# Electronic_Board_Schematic.net
KiCad netlist of a schematic drawn in Altium Designer
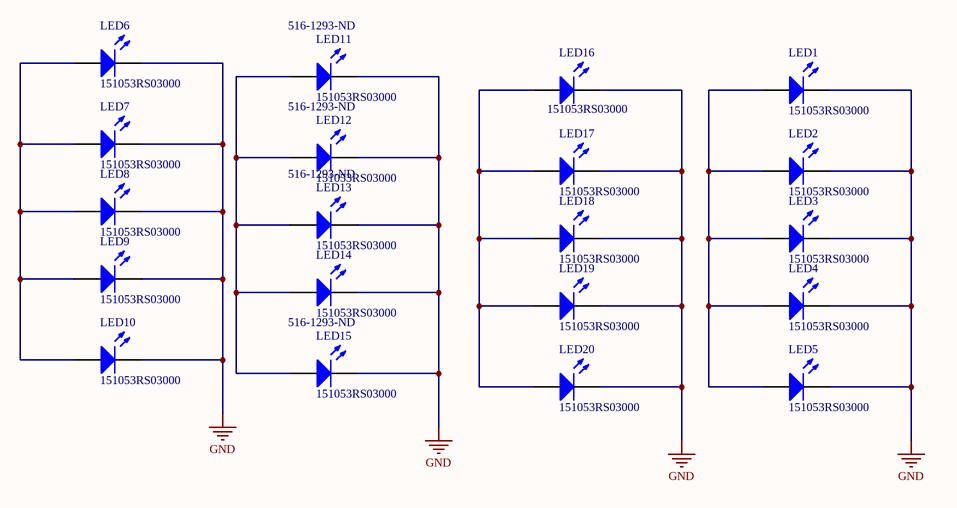
[diagram p0: Electronic_Board_Schematic.SchDoc]

(export (version "E")
  (design (tool "Eeschema 10.0.6"))
  (components
    (comp (ref "LED1")
      (value "151053RS03000")
      (footprint "Type 5mm")
      (description "THT LED round mono-color waterclear,  WL-TMRW ,Red")
      (fields (field (name "MANUFACTURER") "Wuerth Elektronik"))
      (libsource (lib "Altium Content Vault") (part "WE-LED_K1A2-2"))
    )
    (comp (ref "LED2")
      (value "151053RS03000")
      (footprint "Type 5mm")
      (description "THT LED round mono-color waterclear,  WL-TMRW ,Red")
      (fields (field (name "MANUFACTURER") "Wuerth Elektronik"))
      (libsource (lib "Altium Content Vault") (part "WE-LED_K1A2-2"))
    )
    (comp (ref "LED3")
      (value "151053RS03000")
      (footprint "Type 5mm")
      (description "THT LED round mono-color waterclear,  WL-TMRW ,Red")
      (fields (field (name "MANUFACTURER") "Wuerth Elektronik"))
      (libsource (lib "Altium Content Vault") (part "WE-LED_K1A2-2"))
    )
    (comp (ref "LED4")
      (value "151053RS03000")
      (footprint "Type 5mm")
      (description "THT LED round mono-color waterclear,  WL-TMRW ,Red")
      (fields (field (name "MANUFACTURER") "Wuerth Elektronik"))
      (libsource (lib "Altium Content Vault") (part "WE-LED_K1A2-2"))
    )
    (comp (ref "LED5")
      (value "151053RS03000")
      (footprint "Type 5mm")
      (description "THT LED round mono-color waterclear,  WL-TMRW ,Red")
      (fields (field (name "MANUFACTURER") "Wuerth Elektronik"))
      (libsource (lib "Altium Content Vault") (part "WE-LED_K1A2-2"))
    )
    (comp (ref "LED6")
      (value "151053RS03000")
      (footprint "Type 5mm")
      (description "THT LED round mono-color waterclear,  WL-TMRW ,Red")
      (fields (field (name "MANUFACTURER") "Wuerth Elektronik"))
      (libsource (lib "Altium Content Vault") (part "WE-LED_K1A2-2"))
    )
    (comp (ref "LED7")
      (value "151053RS03000")
      (footprint "Type 5mm")
      (description "THT LED round mono-color waterclear,  WL-TMRW ,Red")
      (fields (field (name "MANUFACTURER") "Wuerth Elektronik"))
      (libsource (lib "Altium Content Vault") (part "WE-LED_K1A2-2"))
    )
    (comp (ref "LED8")
      (value "151053RS03000")
      (footprint "Type 5mm")
      (description "THT LED round mono-color waterclear,  WL-TMRW ,Red")
      (fields (field (name "MANUFACTURER") "Wuerth Elektronik"))
      (libsource (lib "Altium Content Vault") (part "WE-LED_K1A2-2"))
    )
    (comp (ref "LED9")
      (value "151053RS03000")
      (footprint "Type 5mm")
      (description "THT LED round mono-color waterclear,  WL-TMRW ,Red")
      (fields (field (name "MANUFACTURER") "Wuerth Elektronik"))
      (libsource (lib "Altium Content Vault") (part "WE-LED_K1A2-2"))
    )
    (comp (ref "LED10")
      (value "151053RS03000")
      (footprint "Type 5mm")
      (description "THT LED round mono-color waterclear,  WL-TMRW ,Red")
      (fields (field (name "MANUFACTURER") "Wuerth Elektronik"))
      (libsource (lib "Altium Content Vault") (part "WE-LED_K1A2-2"))
    )
    (comp (ref "LED11")
      (value "151053RS03000")
      (footprint "Type 5mm")
      (description "THT LED round mono-color waterclear,  WL-TMRW ,Red")
      (fields
        (field (name "MANUFACTURER") "Wuerth Elektronik")
        (field (name "SUPPLIER PART NUMBER 1") "516-1293-ND")
        (field (name "MANUFACTURER PART NUMBER") "HLMP-1503")
      )
      (libsource (lib "Altium Content Vault") (part "WE-LED_K1A2-2"))
    )
    (comp (ref "LED12")
      (value "151053RS03000")
      (footprint "Type 5mm")
      (description "THT LED round mono-color waterclear,  WL-TMRW ,Red")
      (fields
        (field (name "MANUFACTURER") "Wuerth Elektronik")
        (field (name "SUPPLIER PART NUMBER 1") "516-1293-ND")
        (field (name "MANUFACTURER PART NUMBER") "HLMP-1503")
      )
      (libsource (lib "Altium Content Vault") (part "WE-LED_K1A2-2"))
    )
    (comp (ref "LED13")
      (value "151053RS03000")
      (footprint "Type 5mm")
      (description "THT LED round mono-color waterclear,  WL-TMRW ,Red")
      (fields
        (field (name "MANUFACTURER") "Wuerth Elektronik")
        (field (name "SUPPLIER PART NUMBER 1") "516-1293-ND")
        (field (name "MANUFACTURER PART NUMBER") "HLMP-1503")
      )
      (libsource (lib "Altium Content Vault") (part "WE-LED_K1A2-2"))
    )
    (comp (ref "LED14")
      (value "151053RS03000")
      (footprint "Type 5mm")
      (description "THT LED round mono-color waterclear,  WL-TMRW ,Red")
      (fields (field (name "MANUFACTURER") "Wuerth Elektronik"))
      (libsource (lib "Altium Content Vault") (part "WE-LED_K1A2-2"))
    )
    (comp (ref "LED15")
      (value "151053RS03000")
      (footprint "Type 5mm")
      (description "THT LED round mono-color waterclear,  WL-TMRW ,Red")
      (fields
        (field (name "MANUFACTURER") "Wuerth Elektronik")
        (field (name "SUPPLIER PART NUMBER 1") "516-1293-ND")
        (field (name "MANUFACTURER PART NUMBER") "HLMP-1503")
      )
      (libsource (lib "Altium Content Vault") (part "WE-LED_K1A2-2"))
    )
    (comp (ref "LED16")
      (value "151053RS03000")
      (footprint "Type 5mm")
      (description "THT LED round mono-color waterclear,  WL-TMRW ,Red")
      (fields (field (name "MANUFACTURER") "Wuerth Elektronik"))
      (libsource (lib "Altium Content Vault") (part "WE-LED_K1A2-2"))
    )
    (comp (ref "LED17")
      (value "151053RS03000")
      (footprint "Type 5mm")
      (description "THT LED round mono-color waterclear,  WL-TMRW ,Red")
      (fields (field (name "MANUFACTURER") "Wuerth Elektronik"))
      (libsource (lib "Altium Content Vault") (part "WE-LED_K1A2-2"))
    )
    (comp (ref "LED18")
      (value "151053RS03000")
      (footprint "Type 5mm")
      (description "THT LED round mono-color waterclear,  WL-TMRW ,Red")
      (fields (field (name "MANUFACTURER") "Wuerth Elektronik"))
      (libsource (lib "Altium Content Vault") (part "WE-LED_K1A2-2"))
    )
    (comp (ref "LED19")
      (value "151053RS03000")
      (footprint "Type 5mm")
      (description "THT LED round mono-color waterclear,  WL-TMRW ,Red")
      (fields (field (name "MANUFACTURER") "Wuerth Elektronik"))
      (libsource (lib "Altium Content Vault") (part "WE-LED_K1A2-2"))
    )
    (comp (ref "LED20")
      (value "151053RS03000")
      (footprint "Type 5mm")
      (description "THT LED round mono-color waterclear,  WL-TMRW ,Red")
      (fields (field (name "MANUFACTURER") "Wuerth Elektronik"))
      (libsource (lib "Altium Content Vault") (part "WE-LED_K1A2-2"))
    )
  )
  (nets
    (net (code "1") (name "GND") (class "Default")
      (node (ref "LED1") (pin "1") (pinfunction "K_1") (pintype "passive"))
      (node (ref "LED10") (pin "1") (pinfunction "K_1") (pintype "passive"))
      (node (ref "LED11") (pin "1") (pinfunction "K_1") (pintype "passive"))
      (node (ref "LED12") (pin "1") (pinfunction "K_1") (pintype "passive"))
      (node (ref "LED13") (pin "1") (pinfunction "K_1") (pintype "passive"))
      (node (ref "LED14") (pin "1") (pinfunction "K_1") (pintype "passive"))
      (node (ref "LED15") (pin "1") (pinfunction "K_1") (pintype "passive"))
      (node (ref "LED16") (pin "1") (pinfunction "K_1") (pintype "passive"))
      (node (ref "LED17") (pin "1") (pinfunction "K_1") (pintype "passive"))
      (node (ref "LED18") (pin "1") (pinfunction "K_1") (pintype "passive"))
      (node (ref "LED19") (pin "1") (pinfunction "K_1") (pintype "passive"))
      (node (ref "LED2") (pin "1") (pinfunction "K_1") (pintype "passive"))
      (node (ref "LED20") (pin "1") (pinfunction "K_1") (pintype "passive"))
      (node (ref "LED3") (pin "1") (pinfunction "K_1") (pintype "passive"))
      (node (ref "LED4") (pin "1") (pinfunction "K_1") (pintype "passive"))
      (node (ref "LED5") (pin "1") (pinfunction "K_1") (pintype "passive"))
      (node (ref "LED6") (pin "1") (pinfunction "K_1") (pintype "passive"))
      (node (ref "LED7") (pin "1") (pinfunction "K_1") (pintype "passive"))
      (node (ref "LED8") (pin "1") (pinfunction "K_1") (pintype "passive"))
      (node (ref "LED9") (pin "1") (pinfunction "K_1") (pintype "passive"))
    )
    (net (code "2") (name "Net-(LED1-A)") (class "Default")
      (node (ref "LED1") (pin "2") (pinfunction "A_2") (pintype "passive"))
      (node (ref "LED2") (pin "2") (pinfunction "A_2") (pintype "passive"))
      (node (ref "LED3") (pin "2") (pinfunction "A_2") (pintype "passive"))
      (node (ref "LED4") (pin "2") (pinfunction "A_2") (pintype "passive"))
      (node (ref "LED5") (pin "2") (pinfunction "A_2") (pintype "passive"))
    )
    (net (code "3") (name "Net-(LED10-A)") (class "Default")
      (node (ref "LED10") (pin "2") (pinfunction "A_2") (pintype "passive"))
      (node (ref "LED6") (pin "2") (pinfunction "A_2") (pintype "passive"))
      (node (ref "LED7") (pin "2") (pinfunction "A_2") (pintype "passive"))
      (node (ref "LED8") (pin "2") (pinfunction "A_2") (pintype "passive"))
      (node (ref "LED9") (pin "2") (pinfunction "A_2") (pintype "passive"))
    )
    (net (code "4") (name "Net-(LED11-A)") (class "Default")
      (node (ref "LED11") (pin "2") (pinfunction "A_2") (pintype "passive"))
      (node (ref "LED12") (pin "2") (pinfunction "A_2") (pintype "passive"))
      (node (ref "LED13") (pin "2") (pinfunction "A_2") (pintype "passive"))
      (node (ref "LED14") (pin "2") (pinfunction "A_2") (pintype "passive"))
      (node (ref "LED15") (pin "2") (pinfunction "A_2") (pintype "passive"))
    )
    (net (code "5") (name "Net-(LED16-A)") (class "Default")
      (node (ref "LED16") (pin "2") (pinfunction "A_2") (pintype "passive"))
      (node (ref "LED17") (pin "2") (pinfunction "A_2") (pintype "passive"))
      (node (ref "LED18") (pin "2") (pinfunction "A_2") (pintype "passive"))
      (node (ref "LED19") (pin "2") (pinfunction "A_2") (pintype "passive"))
      (node (ref "LED20") (pin "2") (pinfunction "A_2") (pintype "passive"))
    )
  )
)
